# IPMI.net
KiCad netlist of a schematic drawn in Altium Designer
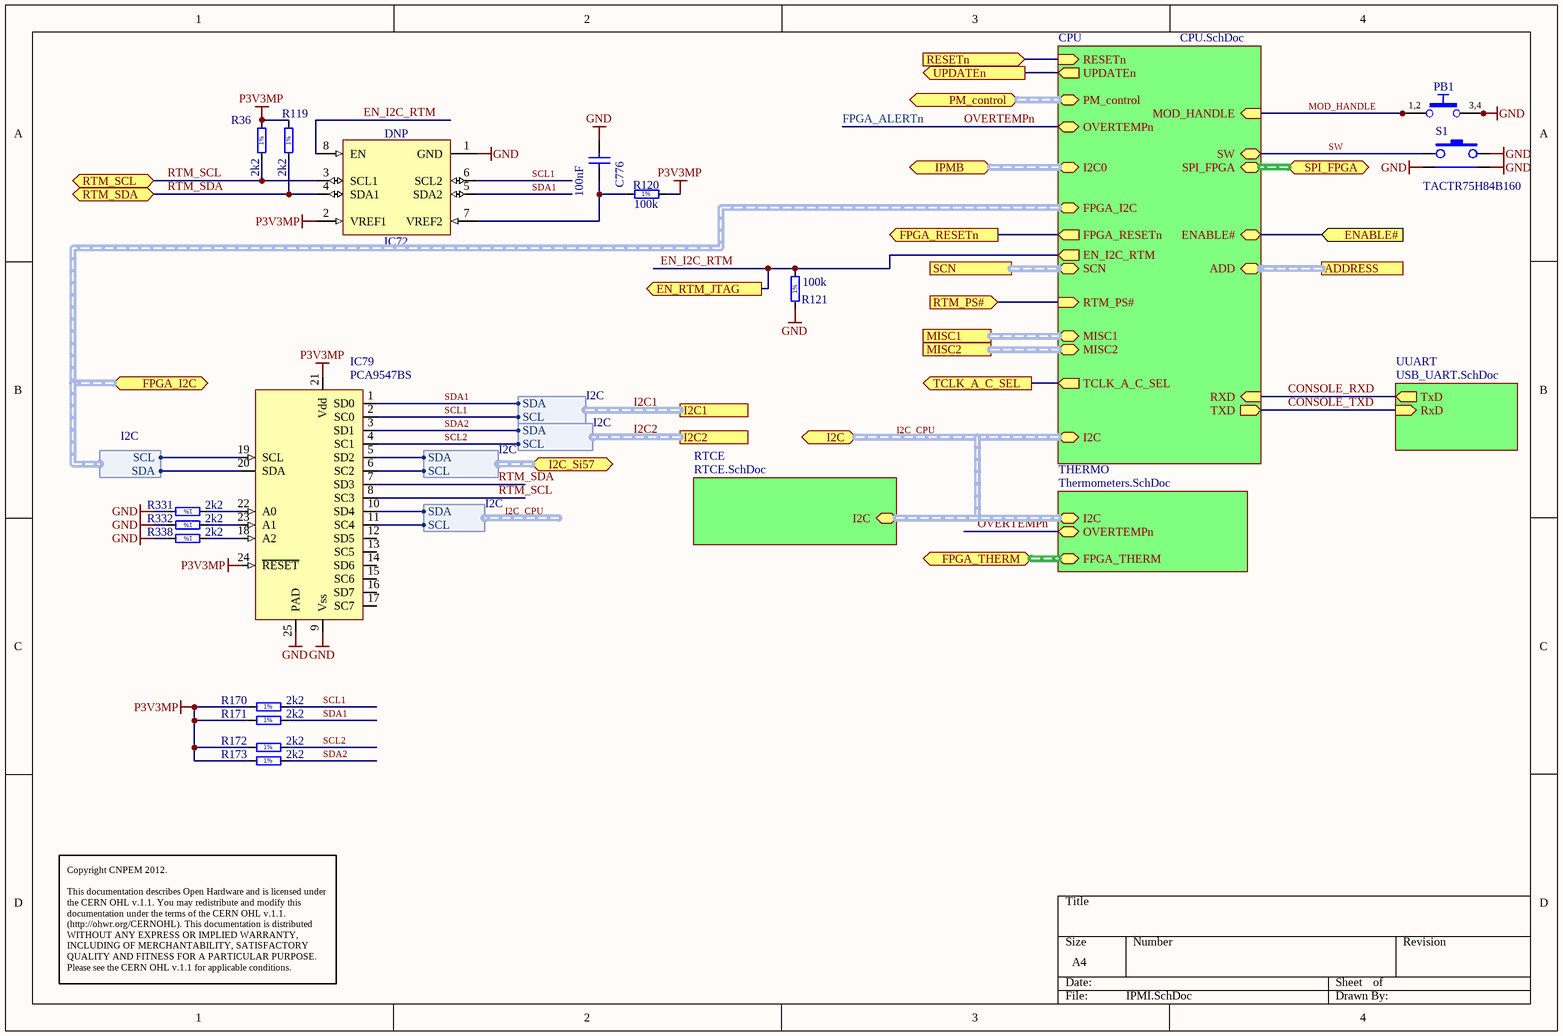
[diagram p0: IPMI.SchDoc]

(export (version "E")
  (design (tool "Eeschema 10.0.6"))
  (components
    (comp (ref "C776")
      (value "100nF")
      (footprint "CAPC0603X33N")
      (description "Non-polarised capacitor")
      (fields
        (field (name "PART NUMBER") "CC0201_100NF_6.3V_10%_X5R")
        (field (name "VOLTAGE") "6.3V")
        (field (name "AUTHOR") "CERN DEM JLC")
      )
      (libsource (lib "Capacitors") (part "Capacitor - non polarized"))
    )
    (comp (ref "IC72")
      (value "DNP")
      (footprint "SOP65P400X130-8N")
      (description "Dual Bidirectional I2C Bus And SMBus Voltage-Level Translator")
      (fields
        (field (name "PART NUMBER") "PCA9306DCTR")
        (field (name "MANUFACTURER") "TEXAS INSTRUMENTS")
        (field (name "AUTHOR") "CERN DEM JLC")
      )
      (libsource (lib "ICs And Semiconductors") (part "PCA9306DC"))
    )
    (comp (ref "IC79")
      (value "PCA9547BS")
      (footprint "HVQFN24")
      (description "8-channel I2C-bus multiplexer with reset")
      (libsource (lib "LIBRARY_SCH") (part "IIC_MUX_PCA9547"))
    )
    (comp (ref "PB1")
      (value "Push Button")
      (footprint "SW_C&K_HDT0001")
      (description "Push-Button Switch SPDT")
      (fields
        (field (name "PART NUMBER") "SW_C&K_HDT0001")
        (field (name "MANUFACTURER") "C&K")
        (field (name "AUTHOR") "CERN DEM JLC")
      )
      (libsource (lib "Eletro-mechanical") (part "PB SPST 12NO-34NO"))
    )
    (comp (ref "R36")
      (value "2k2")
      (footprint "RESC1005X40N")
      (description "Resistor - 1%")
      (fields
        (field (name "PART NUMBER") "R0402_2K2_1%_0.0625W_100PPM")
        (field (name "POWER") "0.0625W")
        (field (name "AUTHOR") "CERN DEM JLC")
      )
      (libsource (lib "Resistors") (part "Resistor - 1%"))
    )
    (comp (ref "R119")
      (value "2k2")
      (footprint "RESC1005X40N")
      (description "Resistor - 1%")
      (fields
        (field (name "PART NUMBER") "R0402_2K2_1%_0.0625W_100PPM")
        (field (name "POWER") "0.0625W")
        (field (name "AUTHOR") "CERN DEM JLC")
      )
      (libsource (lib "Resistors") (part "Resistor - 1%"))
    )
    (comp (ref "R120")
      (value "100k")
      (footprint "RESC1005X40N")
      (description "Resistor - 1%")
      (fields
        (field (name "PART NUMBER") "R0402_100K_1%_0.0625W_100PPM")
        (field (name "POWER") "0.0625W")
        (field (name "AUTHOR") "CERN DEM JLC")
      )
      (libsource (lib "Resistors") (part "Resistor - 1%"))
    )
    (comp (ref "R121")
      (value "100k")
      (footprint "RESC1005X40N")
      (description "Resistor - 1%")
      (fields
        (field (name "PART NUMBER") "R0402_100K_1%_0.0625W_100PPM")
        (field (name "POWER") "0.0625W")
        (field (name "AUTHOR") "CERN DEM JLC")
      )
      (libsource (lib "Resistors") (part "Resistor - 1%"))
    )
    (comp (ref "R170")
      (value "2k2")
      (footprint "RESC1005X40N")
      (description "Resistor - 1%")
      (fields
        (field (name "PART NUMBER") "R0402_2K2_1%_0.0625W_100PPM")
        (field (name "POWER") "0.0625W")
        (field (name "AUTHOR") "CERN DEM JLC")
      )
      (libsource (lib "Resistors") (part "Resistor - 1%"))
    )
    (comp (ref "R171")
      (value "2k2")
      (footprint "RESC1005X40N")
      (description "Resistor - 1%")
      (fields
        (field (name "PART NUMBER") "R0402_2K2_1%_0.0625W_100PPM")
        (field (name "POWER") "0.0625W")
        (field (name "AUTHOR") "CERN DEM JLC")
      )
      (libsource (lib "Resistors") (part "Resistor - 1%"))
    )
    (comp (ref "R172")
      (value "2k2")
      (footprint "RESC1005X40N")
      (description "Resistor - 1%")
      (fields
        (field (name "PART NUMBER") "R0402_2K2_1%_0.0625W_100PPM")
        (field (name "POWER") "0.0625W")
        (field (name "AUTHOR") "CERN DEM JLC")
      )
      (libsource (lib "Resistors") (part "Resistor - 1%"))
    )
    (comp (ref "R173")
      (value "2k2")
      (footprint "RESC1005X40N")
      (description "Resistor - 1%")
      (fields
        (field (name "PART NUMBER") "R0402_2K2_1%_0.0625W_100PPM")
        (field (name "POWER") "0.0625W")
        (field (name "AUTHOR") "CERN DEM JLC")
      )
      (libsource (lib "Resistors") (part "Resistor - 1%"))
    )
    (comp (ref "R331")
      (value "2k2")
      (footprint "RESC1005X40N")
      (description "Resistor - 1%")
      (fields
        (field (name "PART NUMBER") "R0402_2K2_1%_0.0625W_100PPM")
        (field (name "POWER") "0.0625W")
        (field (name "AUTHOR") "CERN DEM JLC")
      )
      (libsource (lib "Resistors") (part "Resistor - 1%"))
    )
    (comp (ref "R332")
      (value "2k2")
      (footprint "RESC1005X40N")
      (description "Resistor - 1%")
      (fields
        (field (name "PART NUMBER") "R0402_2K2_1%_0.0625W_100PPM")
        (field (name "POWER") "0.0625W")
        (field (name "AUTHOR") "CERN DEM JLC")
      )
      (libsource (lib "Resistors") (part "Resistor - 1%"))
    )
    (comp (ref "R338")
      (value "2k2")
      (footprint "RESC1005X40N")
      (description "Resistor - 1%")
      (fields
        (field (name "PART NUMBER") "R0402_2K2_1%_0.0625W_100PPM")
        (field (name "POWER") "0.0625W")
        (field (name "AUTHOR") "CERN DEM JLC")
      )
      (libsource (lib "Resistors") (part "Resistor - 1%"))
    )
    (comp (ref "S1")
      (value "TACTR75H84B160")
      (footprint "PB_ALPS_SKHHLQA010")
      (description "Push button")
      (libsource (lib "LIBRARY_SCH") (part "SW-PB_RA_5.8mm"))
    )
  )
  (nets
    (net (code "18") (name "/EN_I2C_RTM") (class "Default")
      (node (ref "IC72") (pin "8") (pinfunction "EN_8") (pintype "input"))
      (node (ref "R121") (pin "2") (pinfunction "2_2") (pintype "passive"))
    )
    (net (code "28") (name "/MOD_HANDLE") (class "Default")
      (node (ref "PB1") (pin "1") (pinfunction "1_1") (pintype "passive"))
      (node (ref "PB1") (pin "2") (pinfunction "2_2") (pintype "passive"))
    )
    (net (code "32") (name "/RTM_SCL") (class "Default")
      (node (ref "IC72") (pin "3") (pinfunction "SCL1_3") (pintype "bidirectional"))
      (node (ref "IC79") (pin "8") (pinfunction "SC3_8") (pintype "bidirectional"))
      (node (ref "R36") (pin "1") (pinfunction "1_1") (pintype "passive"))
    )
    (net (code "33") (name "/RTM_SDA") (class "Default")
      (node (ref "IC72") (pin "4") (pinfunction "SDA1_4") (pintype "bidirectional"))
      (node (ref "IC79") (pin "7") (pinfunction "SD3_7") (pintype "bidirectional"))
      (node (ref "R119") (pin "1") (pinfunction "1_1") (pintype "passive"))
    )
    (net (code "34") (name "/SCL1") (class "Default")
      (node (ref "IC72") (pin "6") (pinfunction "SCL2_6") (pintype "bidirectional"))
      (node (ref "IC79") (pin "2") (pinfunction "SC0_2") (pintype "bidirectional"))
      (node (ref "R170") (pin "2") (pinfunction "2_2") (pintype "passive"))
    )
    (net (code "35") (name "/SCL2") (class "Default")
      (node (ref "IC79") (pin "4") (pinfunction "SC1_4") (pintype "bidirectional"))
      (node (ref "R172") (pin "2") (pinfunction "2_2") (pintype "passive"))
    )
    (net (code "37") (name "/SDA1") (class "Default")
      (node (ref "IC72") (pin "5") (pinfunction "SDA2_5") (pintype "bidirectional"))
      (node (ref "IC79") (pin "1") (pinfunction "SD0_1") (pintype "bidirectional"))
      (node (ref "R171") (pin "2") (pinfunction "2_2") (pintype "passive"))
    )
    (net (code "38") (name "/SDA2") (class "Default")
      (node (ref "IC79") (pin "3") (pinfunction "SD1_3") (pintype "bidirectional"))
      (node (ref "R173") (pin "2") (pinfunction "2_2") (pintype "passive"))
    )
    (net (code "40") (name "/SW") (class "Default")
      (node (ref "S1") (pin "1") (pinfunction "1_1") (pintype "passive"))
    )
    (net (code "45") (name "GND") (class "Default")
      (node (ref "C776") (pin "2") (pinfunction "2_2") (pintype "passive"))
      (node (ref "IC72") (pin "1") (pinfunction "GND_1") (pintype "power_in"))
      (node (ref "IC79") (pin "25") (pinfunction "PAD_25") (pintype "power_in"))
      (node (ref "IC79") (pin "9") (pinfunction "Vss_9") (pintype "power_in"))
      (node (ref "PB1") (pin "3") (pinfunction "3_3") (pintype "passive"))
      (node (ref "PB1") (pin "4") (pinfunction "4_4") (pintype "passive"))
      (node (ref "R121") (pin "1") (pinfunction "1_1") (pintype "passive"))
      (node (ref "R331") (pin "2") (pinfunction "2_2") (pintype "passive"))
      (node (ref "R332") (pin "2") (pinfunction "2_2") (pintype "passive"))
      (node (ref "R338") (pin "2") (pinfunction "2_2") (pintype "passive"))
      (node (ref "S1") (pin "2") (pinfunction "2_2") (pintype "passive"))
      (node (ref "S1") (pin "3") (pinfunction "3_3") (pintype "passive"))
      (node (ref "S1") (pin "4") (pinfunction "4_4") (pintype "passive"))
    )
    (net (code "46") (name "Net-(IC72-VREF2)") (class "Default")
      (node (ref "C776") (pin "1") (pinfunction "1_1") (pintype "passive"))
      (node (ref "IC72") (pin "7") (pinfunction "VREF2_7") (pintype "input"))
      (node (ref "R120") (pin "1") (pinfunction "1_1") (pintype "passive"))
    )
    (net (code "47") (name "Net-(IC79-A0)") (class "Default")
      (node (ref "IC79") (pin "22") (pinfunction "A0_22") (pintype "input"))
      (node (ref "R331") (pin "1") (pinfunction "1_1") (pintype "passive"))
    )
    (net (code "48") (name "Net-(IC79-A1)") (class "Default")
      (node (ref "IC79") (pin "23") (pinfunction "A1_23") (pintype "input"))
      (node (ref "R332") (pin "1") (pinfunction "1_1") (pintype "passive"))
    )
    (net (code "49") (name "Net-(IC79-A2)") (class "Default")
      (node (ref "IC79") (pin "18") (pinfunction "A2_18") (pintype "input"))
      (node (ref "R338") (pin "1") (pinfunction "1_1") (pintype "passive"))
    )
    (net (code "50") (name "P3V3MP") (class "Default")
      (node (ref "IC72") (pin "2") (pinfunction "VREF1_2") (pintype "input"))
      (node (ref "IC79") (pin "21") (pinfunction "Vdd_21") (pintype "power_in"))
      (node (ref "IC79") (pin "24") (pinfunction "~{RESET}_24") (pintype "input"))
      (node (ref "R119") (pin "2") (pinfunction "2_2") (pintype "passive"))
      (node (ref "R120") (pin "2") (pinfunction "2_2") (pintype "passive"))
      (node (ref "R170") (pin "1") (pinfunction "1_1") (pintype "passive"))
      (node (ref "R171") (pin "1") (pinfunction "1_1") (pintype "passive"))
      (node (ref "R172") (pin "1") (pinfunction "1_1") (pintype "passive"))
      (node (ref "R173") (pin "1") (pinfunction "1_1") (pintype "passive"))
      (node (ref "R36") (pin "2") (pinfunction "2_2") (pintype "passive"))
    )
    (net (code "51") (name "unconnected-(IC79-SC2-Pad6)") (class "Default")
      (node (ref "IC79") (pin "6") (pinfunction "SC2_6") (pintype "bidirectional"))
    )
    (net (code "52") (name "unconnected-(IC79-SC4-Pad11)") (class "Default")
      (node (ref "IC79") (pin "11") (pinfunction "SC4_11") (pintype "bidirectional"))
    )
    (net (code "53") (name "unconnected-(IC79-SC5-Pad13)") (class "Default")
      (node (ref "IC79") (pin "13") (pinfunction "SC5_13") (pintype "bidirectional"))
    )
    (net (code "54") (name "unconnected-(IC79-SC6-Pad15)") (class "Default")
      (node (ref "IC79") (pin "15") (pinfunction "SC6_15") (pintype "bidirectional"))
    )
    (net (code "55") (name "unconnected-(IC79-SC7-Pad17)") (class "Default")
      (node (ref "IC79") (pin "17") (pinfunction "SC7_17") (pintype "bidirectional"))
    )
    (net (code "56") (name "unconnected-(IC79-SCL-Pad19)") (class "Default")
      (node (ref "IC79") (pin "19") (pinfunction "SCL_19") (pintype "input"))
    )
    (net (code "57") (name "unconnected-(IC79-SD2-Pad5)") (class "Default")
      (node (ref "IC79") (pin "5") (pinfunction "SD2_5") (pintype "bidirectional"))
    )
    (net (code "58") (name "unconnected-(IC79-SD4-Pad10)") (class "Default")
      (node (ref "IC79") (pin "10") (pinfunction "SD4_10") (pintype "bidirectional"))
    )
    (net (code "59") (name "unconnected-(IC79-SD5-Pad12)") (class "Default")
      (node (ref "IC79") (pin "12") (pinfunction "SD5_12") (pintype "bidirectional"))
    )
    (net (code "60") (name "unconnected-(IC79-SD6-Pad14)") (class "Default")
      (node (ref "IC79") (pin "14") (pinfunction "SD6_14") (pintype "bidirectional"))
    )
    (net (code "61") (name "unconnected-(IC79-SD7-Pad16)") (class "Default")
      (node (ref "IC79") (pin "16") (pinfunction "SD7_16") (pintype "bidirectional"))
    )
    (net (code "62") (name "unconnected-(IC79-SDA-Pad20)") (class "Default")
      (node (ref "IC79") (pin "20") (pinfunction "SDA_20") (pintype "bidirectional"))
    )
  )
)
